# Vreg.net
KiCad netlist of a schematic drawn in Altium Designer
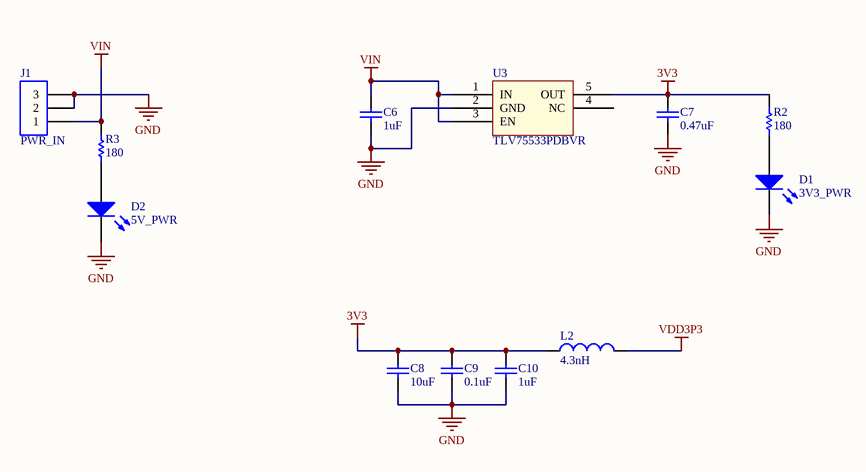
[diagram p0: Vreg.SchDoc]

(export (version "E")
  (design (tool "Eeschema 10.0.6"))
  (components
    (comp (ref "C6")
      (value "1uF")
      (footprint "C0805")
      (description "0805 1 uF 25 V ±10 % Tolerance X7R SMT Multilayer Ceramic Capacitor")
      (fields (field (name "MANUFACTURER PART NUMBER") "CC0805KKX7R8BB105"))
      (libsource (lib "CommunityVault") (part "CAP-NP-2"))
    )
    (comp (ref "C7")
      (value "0.47uF")
      (footprint "CAPC1608X90X35ML15T15")
      (description "CL10 Series 0.47 uF 16 V ±10 % Tolerance X7R SMT Multilayer Ceramic Capacitor")
      (libsource (lib "CommunityVault") (part "SYM-55ff9c78cd6f8a38-1"))
    )
    (comp (ref "C8")
      (value "10uF")
      (footprint "PCB-3l8viaoeo84t9gm70k7i-1")
      (description "Cap Ceramic 10uF 25V X5R 10% SMD 0805 85C Paper T/R")
      (fields (field (name "MANUFACTURER PART NUMBER") "TMK212BBJ106KG-T"))
      (libsource (lib "CommunityVault") (part "CAP-2"))
    )
    (comp (ref "C9")
      (value "0.1uF")
      (footprint "PCB-oygqt4xf3sesynjclq4r-1")
      (description "0.1uF, ±10%, 50V, X7R, 0805, Multilayer Ceramic Capacitor")
      (fields (field (name "MANUFACTURER PART NUMBER") "CL21B104KBCNNNC"))
      (libsource (lib "CommunityVault") (part "SYM-94265da154d84be1-1"))
    )
    (comp (ref "C10")
      (value "1uF")
      (footprint "C0805")
      (description "0805 1 uF 25 V ±10 % Tolerance X7R SMT Multilayer Ceramic Capacitor")
      (fields (field (name "MANUFACTURER PART NUMBER") "CC0805KKX7R8BB105"))
      (libsource (lib "CommunityVault") (part "CAP-NP-2"))
    )
    (comp (ref "D1")
      (value "3V3_PWR")
      (footprint "PCB-1544848-1")
      (description "Blue 1.6 x 0.8 x 0.3 mm 130° Clear 180 mcd 3.8 V Surface Mount LED")
      (fields (field (name "MANUFACTURER PART NUMBER") "LTST-C194TBKT"))
      (libsource (lib "CommunityVault") (part "SYM-b3017a03f2726cc6-1"))
    )
    (comp (ref "D2")
      (value "5V_PWR")
      (footprint "DIOM1608X06N")
      (description "LED; SMD; 0603; red; 18-54mcd; 1.6x0.8x0.55mm; 130°; 2÷2.4V; 20mA")
      (libsource (lib "CommunityVault") (part "SYM-4ddf84dd0cad9218-5"))
    )
    (comp (ref "J1")
      (value "PWR_IN")
      (footprint "ADAM-ADC-002-3_V")
      (description "DC Power Connectors DC POWER JACK 2.5MM PIN TYPE 002")
      (fields (field (name "MANUFACTURER PART NUMBER") "ADC-002-2"))
      (libsource (lib "CommunityVault") (part "ADAM-ADC-002-3"))
    )
    (comp (ref "L2")
      (value "4.3nH")
      (footprint "PCB-vetezry5jn2cqs6s1af8-1")
      (description "Surface Mount High Frequency Inductor, LQW15AN Series, 4.3 nH, 0.1nH, 0402 [1005 Metric], 10 GHz")
      (fields (field (name "MANUFACTURER PART NUMBER") "LQW15AN4N3B00D"))
      (libsource (lib "CommunityVault") (part "SYM-e5012c7543d03ac6-1"))
    )
    (comp (ref "R2")
      (value "180")
      (footprint "RESC2013X60X30NL20T20")
      (description "Thick Film Resistors - SMD 1/8watts 180ohms 1%")
      (fields (field (name "MANUFACTURER PART NUMBER") "RK73H2ATTD1800F"))
      (libsource (lib "CommunityVault") (part "RES-2"))
    )
    (comp (ref "R3")
      (value "180")
      (footprint "RESC2013X60X30NL20T20")
      (description "Thick Film Resistors - SMD 1/8watts 180ohms 1%")
      (fields (field (name "MANUFACTURER PART NUMBER") "RK73H2ATTD1800F"))
      (libsource (lib "CommunityVault") (part "RES-2"))
    )
    (comp (ref "U3")
      (value "TLV75533PDBVR")
      (footprint "PCB-9xapb279xxlk04njnstk-1")
      (description "500-mA low-IQ small-size low-dropout (LDO) regulator 5-SOT-23 -40 to 125")
      (libsource (lib "CommunityVault") (part "SYM-a508697234f37acf-1"))
    )
  )
  (nets
    (net (code "1") (name "3V3") (class "Default")
      (node (ref "C10") (pin "1") (pinfunction "1_1") (pintype "passive"))
      (node (ref "C7") (pin "2") (pinfunction "2_2") (pintype "passive"))
      (node (ref "C8") (pin "2") (pinfunction "2_2") (pintype "passive"))
      (node (ref "C9") (pin "2") (pinfunction "2_2") (pintype "passive"))
      (node (ref "L2") (pin "1") (pinfunction "1_1") (pintype "passive"))
      (node (ref "R2") (pin "2") (pinfunction "2_2") (pintype "passive"))
      (node (ref "U3") (pin "5") (pinfunction "OUT_5") (pintype "passive"))
    )
    (net (code "2") (name "GND") (class "Default")
      (node (ref "C10") (pin "2") (pinfunction "2_2") (pintype "passive"))
      (node (ref "C6") (pin "2") (pinfunction "2_2") (pintype "passive"))
      (node (ref "C7") (pin "1") (pinfunction "1_1") (pintype "passive"))
      (node (ref "C8") (pin "1") (pinfunction "1_1") (pintype "passive"))
      (node (ref "C9") (pin "1") (pinfunction "1_1") (pintype "passive"))
      (node (ref "D1") (pin "2") (pinfunction "K_2") (pintype "passive"))
      (node (ref "D2") (pin "K") (pinfunction "K_K") (pintype "passive"))
      (node (ref "J1") (pin "2") (pinfunction "2_2") (pintype "passive"))
      (node (ref "J1") (pin "3") (pinfunction "3_3") (pintype "passive"))
      (node (ref "U3") (pin "2") (pinfunction "GND_2") (pintype "passive"))
    )
    (net (code "3") (name "Net-(D1-A)") (class "Default")
      (node (ref "D1") (pin "1") (pinfunction "A_1") (pintype "passive"))
      (node (ref "R2") (pin "1") (pinfunction "1_1") (pintype "passive"))
    )
    (net (code "4") (name "Net-(D2-PadA)") (class "Default")
      (node (ref "D2") (pin "A") (pinfunction "A_A") (pintype "passive"))
      (node (ref "R3") (pin "1") (pinfunction "1_1") (pintype "passive"))
    )
    (net (code "5") (name "VDD3P3") (class "Default")
      (node (ref "L2") (pin "2") (pinfunction "2_2") (pintype "passive"))
    )
    (net (code "6") (name "VIN") (class "Default")
      (node (ref "C6") (pin "1") (pinfunction "1_1") (pintype "passive"))
      (node (ref "J1") (pin "1") (pinfunction "1_1") (pintype "passive"))
      (node (ref "R3") (pin "2") (pinfunction "2_2") (pintype "passive"))
      (node (ref "U3") (pin "1") (pinfunction "IN_1") (pintype "passive"))
      (node (ref "U3") (pin "3") (pinfunction "EN_3") (pintype "passive"))
    )
    (net (code "7") (name "unconnected-(U3-NC-Pad4)") (class "Default")
      (node (ref "U3") (pin "4") (pinfunction "NC_4") (pintype "passive"))
    )
  )
)
